# FlightPCB.net
KiCad netlist of a schematic drawn in EAGLE
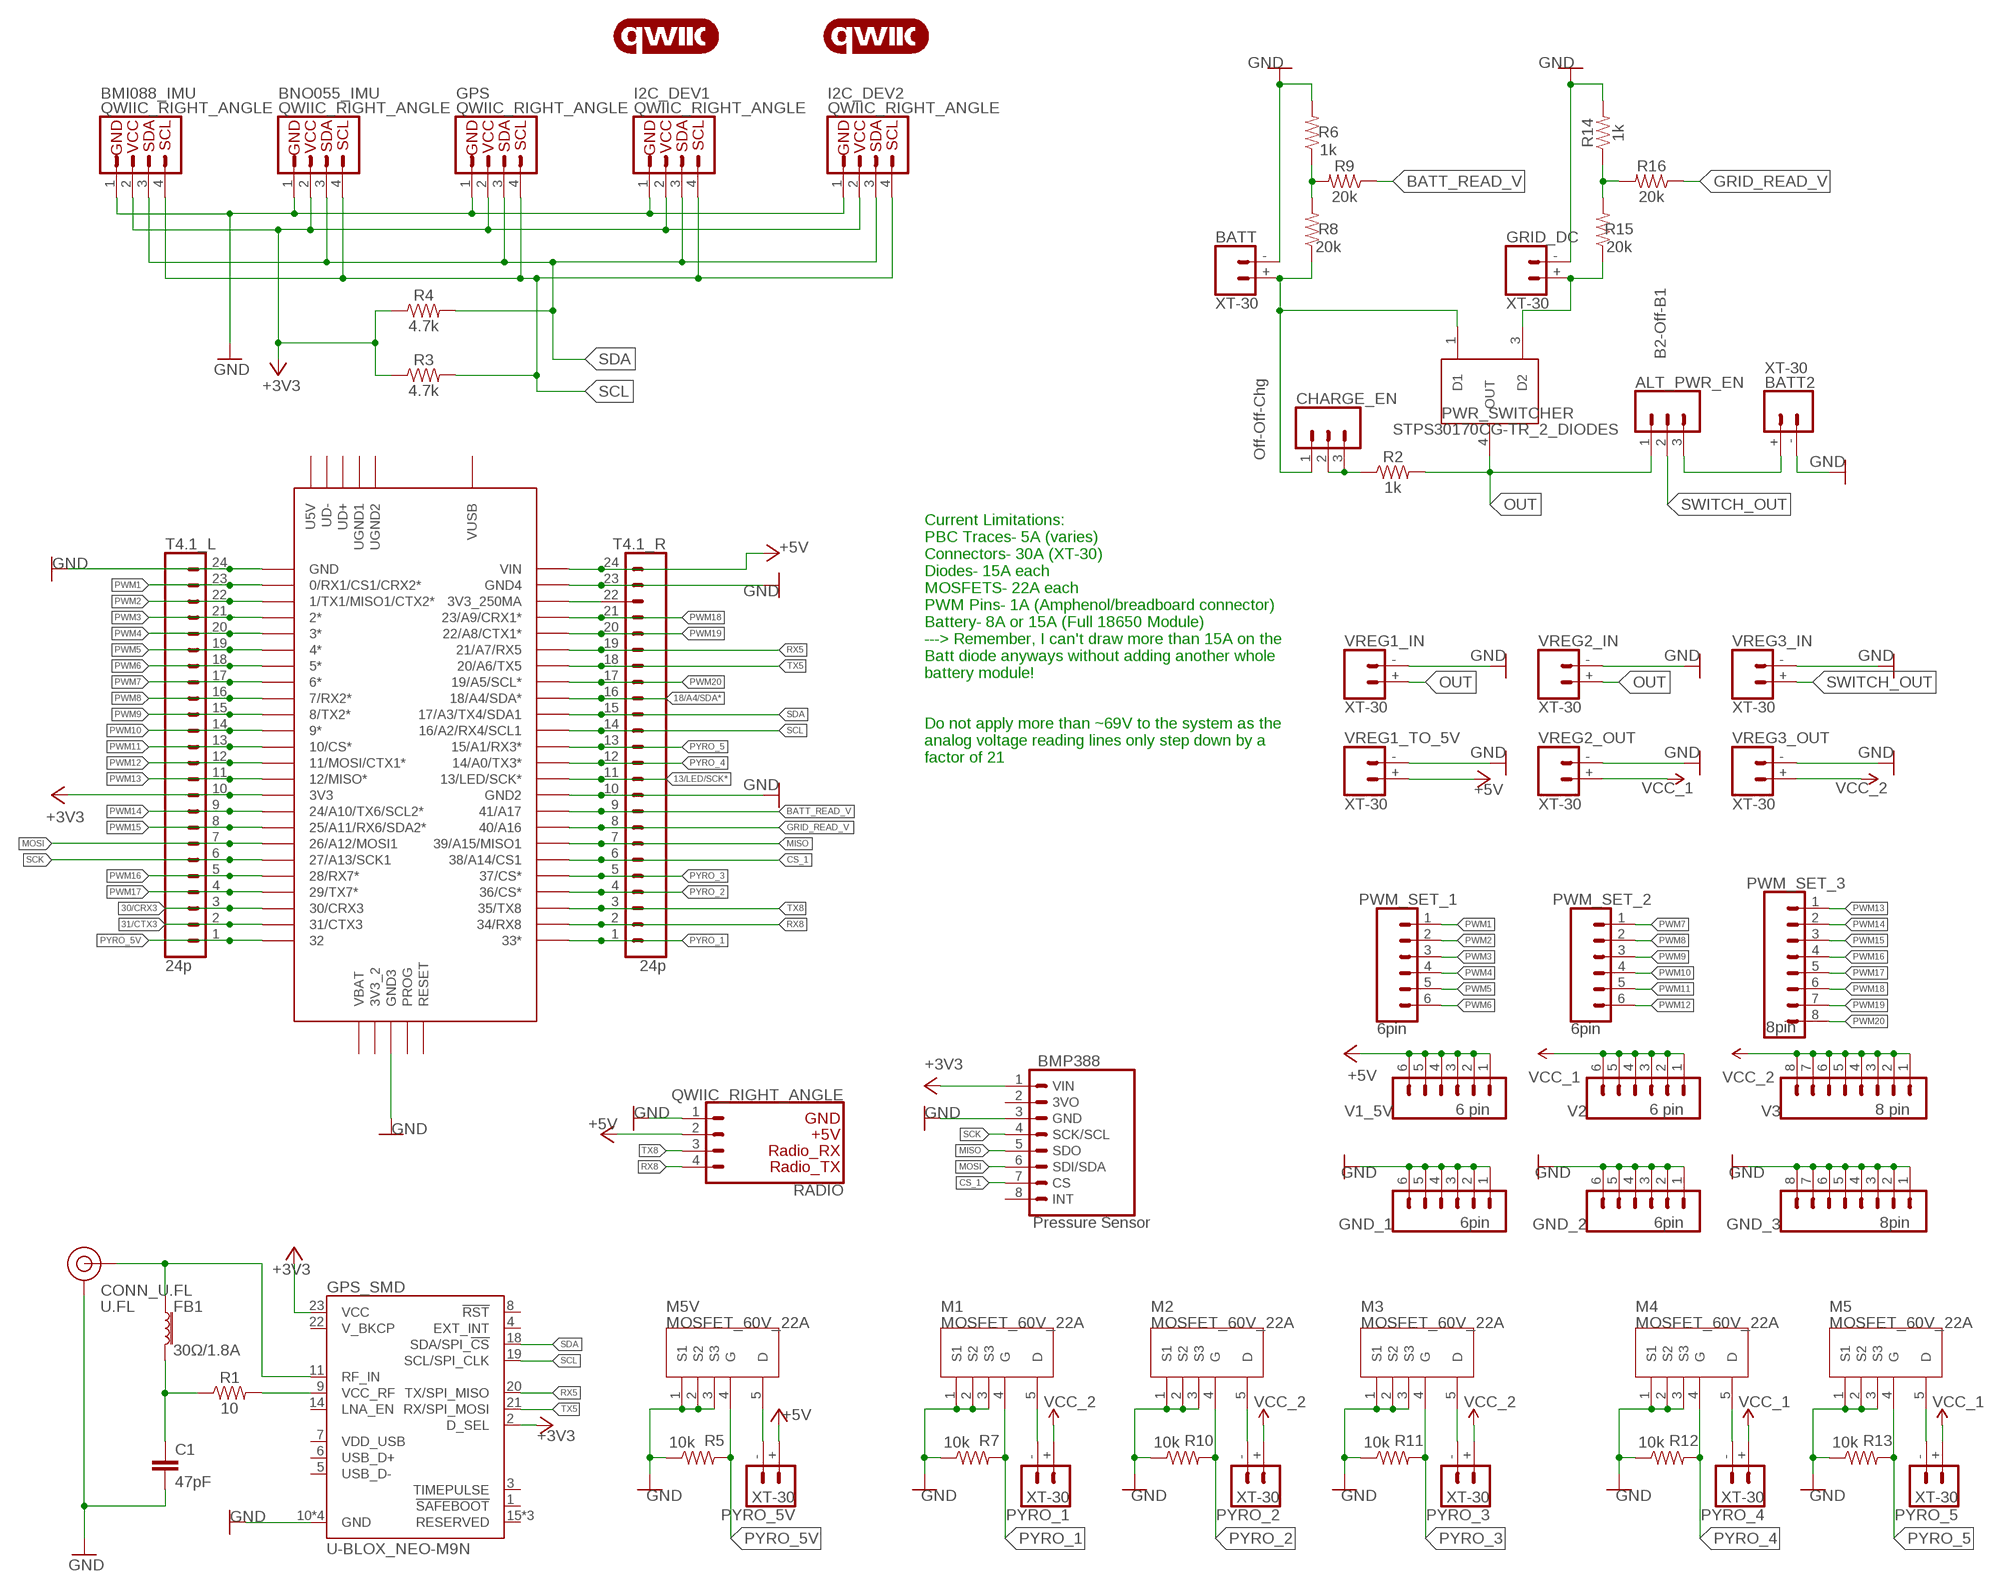
[diagram p0: schematic, sheet 1]

(export (version "E")
  (design (tool "Eeschema 10.0.6"))
  (components
    (comp (ref "ALT_PWR_EN")
      (value "B2-Off-B1")
      (footprint "eagle-import:1X03_SLIDE_SWITCH_EG5137")
      (libsource (lib "eagle-import") (part "CONN_03_SLIDE_SWITCH_EG5137"))
    )
    (comp (ref "BATT")
      (value "XT-30")
      (footprint "eagle-import:1X02_BIG_XT-30")
      (libsource (lib "eagle-import") (part "CONN_02_XT-30_CONNECTOR1X02_XT-30"))
    )
    (comp (ref "BATT2")
      (value "XT-30")
      (footprint "eagle-import:1X02_BIG_XT-30")
      (libsource (lib "eagle-import") (part "CONN_02_XT-30_CONNECTOR1X02_XT-30"))
    )
    (comp (ref "BMI088_IMU")
      (value "QWIIC_RIGHT_ANGLE")
      (footprint "eagle-import:JST04_1MM_RA")
      (libsource (lib "eagle-import") (part "QWIIC_CONNECTORJS-1MM"))
    )
    (comp (ref "BMP388")
      (value "Pressure Sensor")
      (footprint "eagle-import:1X08_FEMALE_LOCK")
      (libsource (lib "eagle-import") (part "CONN_08_BMP388_MODIFIEDFEMALE_LOCK"))
    )
    (comp (ref "BNO055_IMU")
      (value "QWIIC_RIGHT_ANGLE")
      (footprint "eagle-import:JST04_1MM_RA")
      (libsource (lib "eagle-import") (part "QWIIC_CONNECTORJS-1MM"))
    )
    (comp (ref "C1")
      (value "47pF")
      (footprint "eagle-import:0603")
      (libsource (lib "eagle-import") (part "47PF-0603-50V-5%"))
    )
    (comp (ref "CHARGE_EN")
      (value "Off-Off-Chg")
      (footprint "eagle-import:1X03_SLIDE_SWITCH_EG5137")
      (libsource (lib "eagle-import") (part "CONN_03_SLIDE_SWITCH_EG5137"))
    )
    (comp (ref "CONN_U.FL")
      (value "U.FL")
      (footprint "eagle-import:U.FL")
      (libsource (lib "eagle-import") (part "U.FL2PIN"))
    )
    (comp (ref "FB1")
      (value "30Ω/1.8A")
      (footprint "eagle-import:0603")
      (libsource (lib "eagle-import") (part "FERRITE_BEAD-0603"))
    )
    (comp (ref "GND_1")
      (value "6pin")
      (footprint "eagle-import:1X06_LOCK")
      (libsource (lib "eagle-import") (part "CONN_06LOCK"))
    )
    (comp (ref "GND_2")
      (value "6pin")
      (footprint "eagle-import:1X06_LOCK")
      (libsource (lib "eagle-import") (part "CONN_06LOCK"))
    )
    (comp (ref "GND_3")
      (value "8pin")
      (footprint "eagle-import:1X08_LOCK")
      (libsource (lib "eagle-import") (part "CONN_08LOCK"))
    )
    (comp (ref "GPS")
      (value "QWIIC_RIGHT_ANGLE")
      (footprint "eagle-import:JST04_1MM_RA")
      (libsource (lib "eagle-import") (part "QWIIC_CONNECTORJS-1MM"))
    )
    (comp (ref "GPS_SMD")
      (value "U-BLOX_NEO-M9N")
      (footprint "eagle-import:NEO-M9N_M8T_M8U")
      (libsource (lib "eagle-import") (part "U-BLOX_NEO-M9N"))
    )
    (comp (ref "GRID_DC")
      (value "XT-30")
      (footprint "eagle-import:1X02_BIG_XT-30")
      (libsource (lib "eagle-import") (part "CONN_02_XT-30_CONNECTOR1X02_XT-30"))
    )
    (comp (ref "I2C_DEV1")
      (value "QWIIC_RIGHT_ANGLE")
      (footprint "eagle-import:JST04_1MM_RA")
      (libsource (lib "eagle-import") (part "QWIIC_CONNECTORJS-1MM"))
    )
    (comp (ref "I2C_DEV2")
      (value "QWIIC_RIGHT_ANGLE")
      (footprint "eagle-import:JST04_1MM_RA")
      (libsource (lib "eagle-import") (part "QWIIC_CONNECTORJS-1MM"))
    )
    (comp (ref "LOGO1")
      (value "QWIIC_LOGO_CONNECTOR")
      (footprint "eagle-import:QWIIC_5.5MM")
      (libsource (lib "eagle-import") (part "QWIIC_LOGO_CONNECTOR"))
    )
    (comp (ref "LOGO2")
      (value "QWIIC_LOGO_CONNECTOR")
      (footprint "eagle-import:QWIIC_5.5MM")
      (libsource (lib "eagle-import") (part "QWIIC_LOGO_CONNECTOR"))
    )
    (comp (ref "M1")
      (value "MOSFET_60V_22A")
      (footprint "eagle-import:TO127P600X120-5N")
      (libsource (lib "eagle-import") (part "MOSFET_60V_22A"))
    )
    (comp (ref "M2")
      (value "MOSFET_60V_22A")
      (footprint "eagle-import:TO127P600X120-5N")
      (libsource (lib "eagle-import") (part "MOSFET_60V_22A"))
    )
    (comp (ref "M3")
      (value "MOSFET_60V_22A")
      (footprint "eagle-import:TO127P600X120-5N")
      (libsource (lib "eagle-import") (part "MOSFET_60V_22A"))
    )
    (comp (ref "M4")
      (value "MOSFET_60V_22A")
      (footprint "eagle-import:TO127P600X120-5N")
      (libsource (lib "eagle-import") (part "MOSFET_60V_22A"))
    )
    (comp (ref "M5")
      (value "MOSFET_60V_22A")
      (footprint "eagle-import:TO127P600X120-5N")
      (libsource (lib "eagle-import") (part "MOSFET_60V_22A"))
    )
    (comp (ref "M5V")
      (value "MOSFET_60V_22A")
      (footprint "eagle-import:TO127P600X120-5N")
      (libsource (lib "eagle-import") (part "MOSFET_60V_22A"))
    )
    (comp (ref "PWM_SET_1")
      (value "6pin")
      (footprint "eagle-import:1X06_LOCK")
      (libsource (lib "eagle-import") (part "CONN_06LOCK"))
    )
    (comp (ref "PWM_SET_2")
      (value "6pin")
      (footprint "eagle-import:1X06_LOCK")
      (libsource (lib "eagle-import") (part "CONN_06LOCK"))
    )
    (comp (ref "PWM_SET_3")
      (value "8pin")
      (footprint "eagle-import:1X08_LOCK")
      (libsource (lib "eagle-import") (part "CONN_08LOCK"))
    )
    (comp (ref "PWR_SWITCHER")
      (value "STPS30170CG-TR_2_DIODES")
      (footprint "eagle-import:TO-263-3_PACKAGE_MIDDLE_PIN_REMOVED")
      (libsource (lib "eagle-import") (part "STPS30170CG-TR_2_DIODES"))
    )
    (comp (ref "PYRO_1")
      (value "XT-30")
      (footprint "eagle-import:1X02_BIG_XT-30")
      (libsource (lib "eagle-import") (part "CONN_02_XT-30_CONNECTOR1X02_XT-30"))
    )
    (comp (ref "PYRO_2")
      (value "XT-30")
      (footprint "eagle-import:1X02_BIG_XT-30")
      (libsource (lib "eagle-import") (part "CONN_02_XT-30_CONNECTOR1X02_XT-30"))
    )
    (comp (ref "PYRO_3")
      (value "XT-30")
      (footprint "eagle-import:1X02_BIG_XT-30")
      (libsource (lib "eagle-import") (part "CONN_02_XT-30_CONNECTOR1X02_XT-30"))
    )
    (comp (ref "PYRO_4")
      (value "XT-30")
      (footprint "eagle-import:1X02_BIG_XT-30")
      (libsource (lib "eagle-import") (part "CONN_02_XT-30_CONNECTOR1X02_XT-30"))
    )
    (comp (ref "PYRO_5")
      (value "XT-30")
      (footprint "eagle-import:1X02_BIG_XT-30")
      (libsource (lib "eagle-import") (part "CONN_02_XT-30_CONNECTOR1X02_XT-30"))
    )
    (comp (ref "PYRO_5V")
      (value "XT-30")
      (footprint "eagle-import:1X02_BIG_XT-30")
      (libsource (lib "eagle-import") (part "CONN_02_XT-30_CONNECTOR1X02_XT-30"))
    )
    (comp (ref "R1")
      (value "10")
      (footprint "eagle-import:0603")
      (libsource (lib "eagle-import") (part "10OHM-0603-1/10W-1%"))
    )
    (comp (ref "R2")
      (value "1k")
      (footprint "eagle-import:0603")
      (libsource (lib "eagle-import") (part "1KOHM-0603-1/10W-1%"))
    )
    (comp (ref "R3")
      (value "4.7k")
      (footprint "eagle-import:0603")
      (libsource (lib "eagle-import") (part "4.7KOHM-0603-1/10W-1%"))
    )
    (comp (ref "R4")
      (value "4.7k")
      (footprint "eagle-import:0603")
      (libsource (lib "eagle-import") (part "4.7KOHM-0603-1/10W-1%"))
    )
    (comp (ref "R5")
      (value "10k")
      (footprint "eagle-import:0603")
      (libsource (lib "eagle-import") (part "10KOHM-0603-1/10W-1%"))
    )
    (comp (ref "R6")
      (value "1k")
      (footprint "eagle-import:0603")
      (libsource (lib "eagle-import") (part "1KOHM-0603-1/10W-1%"))
    )
    (comp (ref "R7")
      (value "10k")
      (footprint "eagle-import:0603")
      (libsource (lib "eagle-import") (part "10KOHM-0603-1/10W-1%"))
    )
    (comp (ref "R8")
      (value "20k")
      (footprint "eagle-import:0603")
      (libsource (lib "eagle-import") (part "20KOHM-0603-1/10W-1%"))
    )
    (comp (ref "R9")
      (value "20k")
      (footprint "eagle-import:0603")
      (libsource (lib "eagle-import") (part "20KOHM-0603-1/10W-1%"))
    )
    (comp (ref "R10")
      (value "10k")
      (footprint "eagle-import:0603")
      (libsource (lib "eagle-import") (part "10KOHM-0603-1/10W-1%"))
    )
    (comp (ref "R11")
      (value "10k")
      (footprint "eagle-import:0603")
      (libsource (lib "eagle-import") (part "10KOHM-0603-1/10W-1%"))
    )
    (comp (ref "R12")
      (value "10k")
      (footprint "eagle-import:0603")
      (libsource (lib "eagle-import") (part "10KOHM-0603-1/10W-1%"))
    )
    (comp (ref "R13")
      (value "10k")
      (footprint "eagle-import:0603")
      (libsource (lib "eagle-import") (part "10KOHM-0603-1/10W-1%"))
    )
    (comp (ref "R14")
      (value "1k")
      (footprint "eagle-import:0603")
      (libsource (lib "eagle-import") (part "1KOHM-0603-1/10W-1%"))
    )
    (comp (ref "R15")
      (value "20k")
      (footprint "eagle-import:0603")
      (libsource (lib "eagle-import") (part "20KOHM-0603-1/10W-1%"))
    )
    (comp (ref "R16")
      (value "20k")
      (footprint "eagle-import:0603")
      (libsource (lib "eagle-import") (part "20KOHM-0603-1/10W-1%"))
    )
    (comp (ref "RADIO")
      (value "QWIIC_RIGHT_ANGLE")
      (footprint "eagle-import:JST04_1MM_RA")
      (libsource (lib "eagle-import") (part "QWIIC_CONNECTOR_SERIAL_RADIO_MODIFIEDJS-1MM"))
    )
    (comp (ref "T4.1_L")
      (value "24p")
      (footprint "eagle-import:1X24_LOCK")
      (libsource (lib "eagle-import") (part "CONN_24LOCK"))
    )
    (comp (ref "T4.1_R")
      (value "24p")
      (footprint "eagle-import:1X24_LOCK")
      (libsource (lib "eagle-import") (part "CONN_24LOCK"))
    )
    (comp (ref "TEENSY_4.1")
      (value "TEENSY_4.1")
      (footprint "eagle-import:TEENSY_4.1")
      (libsource (lib "eagle-import") (part "TEENSY_4.1"))
    )
    (comp (ref "V1_5V")
      (value "6 pin")
      (footprint "eagle-import:1X06_LOCK")
      (libsource (lib "eagle-import") (part "CONN_06LOCK"))
    )
    (comp (ref "V2")
      (value "6 pin")
      (footprint "eagle-import:1X06_LOCK")
      (libsource (lib "eagle-import") (part "CONN_06LOCK"))
    )
    (comp (ref "V3")
      (value "8 pin")
      (footprint "eagle-import:1X08_LOCK")
      (libsource (lib "eagle-import") (part "CONN_08LOCK"))
    )
    (comp (ref "VREG1_IN")
      (value "XT-30")
      (footprint "eagle-import:1X02_BIG_XT-30")
      (libsource (lib "eagle-import") (part "CONN_02_XT-30_CONNECTOR1X02_XT-30"))
    )
    (comp (ref "VREG1_TO_5V")
      (value "XT-30")
      (footprint "eagle-import:1X02_BIG_XT-30")
      (libsource (lib "eagle-import") (part "CONN_02_XT-30_CONNECTOR1X02_XT-30"))
    )
    (comp (ref "VREG2_IN")
      (value "XT-30")
      (footprint "eagle-import:1X02_BIG_XT-30")
      (libsource (lib "eagle-import") (part "CONN_02_XT-30_CONNECTOR1X02_XT-30"))
    )
    (comp (ref "VREG2_OUT")
      (value "XT-30")
      (footprint "eagle-import:1X02_BIG_XT-30")
      (libsource (lib "eagle-import") (part "CONN_02_XT-30_CONNECTOR1X02_XT-30"))
    )
    (comp (ref "VREG3_IN")
      (value "XT-30")
      (footprint "eagle-import:1X02_BIG_XT-30")
      (libsource (lib "eagle-import") (part "CONN_02_XT-30_CONNECTOR1X02_XT-30"))
    )
    (comp (ref "VREG3_OUT")
      (value "XT-30")
      (footprint "eagle-import:1X02_BIG_XT-30")
      (libsource (lib "eagle-import") (part "CONN_02_XT-30_CONNECTOR1X02_XT-30"))
    )
  )
  (nets
    (net (code "1") (name "+3V3") (class "Default")
      (node (ref "BMI088_IMU") (pin "2") (pinfunction "2_2") (pintype "power_in"))
      (node (ref "BMP388") (pin "1") (pinfunction "VIN_1") (pintype "passive"))
      (node (ref "BNO055_IMU") (pin "2") (pinfunction "2_2") (pintype "power_in"))
      (node (ref "GPS") (pin "2") (pinfunction "2_2") (pintype "power_in"))
      (node (ref "GPS_SMD") (pin "2") (pinfunction "D_SEL_2") (pintype "bidirectional"))
      (node (ref "GPS_SMD") (pin "23") (pinfunction "VCC_23") (pintype "bidirectional"))
      (node (ref "I2C_DEV1") (pin "2") (pinfunction "2_2") (pintype "power_in"))
      (node (ref "I2C_DEV2") (pin "2") (pinfunction "2_2") (pintype "power_in"))
      (node (ref "R3") (pin "1") (pinfunction "1_1") (pintype "passive"))
      (node (ref "R4") (pin "1") (pinfunction "1_1") (pintype "passive"))
      (node (ref "T4.1_L") (pin "10") (pinfunction "10_10") (pintype "passive"))
      (node (ref "TEENSY_4.1") (pin "3V3") (pinfunction "3V3_3V3") (pintype "bidirectional"))
    )
    (net (code "2") (name "+5V") (class "Default")
      (node (ref "PYRO_5V") (pin "+") (pinfunction "+_+") (pintype "passive"))
      (node (ref "RADIO") (pin "2") (pinfunction "2_2") (pintype "power_in"))
      (node (ref "T4.1_R") (pin "24") (pinfunction "24_24") (pintype "passive"))
      (node (ref "TEENSY_4.1") (pin "VIN") (pinfunction "VIN_VIN") (pintype "bidirectional"))
      (node (ref "V1_5V") (pin "1") (pinfunction "1_1") (pintype "passive"))
      (node (ref "V1_5V") (pin "2") (pinfunction "2_2") (pintype "passive"))
      (node (ref "V1_5V") (pin "3") (pinfunction "3_3") (pintype "passive"))
      (node (ref "V1_5V") (pin "4") (pinfunction "4_4") (pintype "passive"))
      (node (ref "V1_5V") (pin "5") (pinfunction "5_5") (pintype "passive"))
      (node (ref "V1_5V") (pin "6") (pinfunction "6_6") (pintype "passive"))
      (node (ref "VREG1_TO_5V") (pin "+") (pinfunction "+_+") (pintype "passive"))
    )
    (net (code "3") (name "13{slash}LED{slash}SCK*") (class "Default")
      (node (ref "T4.1_R") (pin "11") (pinfunction "11_11") (pintype "passive"))
      (node (ref "TEENSY_4.1") (pin "13/LED/SCK*") (pinfunction "13/LED/SCK*_13/LED/SCK*") (pintype "bidirectional"))
    )
    (net (code "4") (name "18{slash}A4{slash}SDA*") (class "Default")
      (node (ref "T4.1_R") (pin "16") (pinfunction "16_16") (pintype "passive"))
      (node (ref "TEENSY_4.1") (pin "18/A4/SDA*") (pinfunction "18/A4/SDA*_18/A4/SDA*") (pintype "bidirectional"))
    )
    (net (code "5") (name "30{slash}CRX3") (class "Default")
      (node (ref "T4.1_L") (pin "3") (pinfunction "3_3") (pintype "passive"))
      (node (ref "TEENSY_4.1") (pin "30/CRX3") (pinfunction "30/CRX3_30/CRX3") (pintype "bidirectional"))
    )
    (net (code "6") (name "31{slash}CTX3") (class "Default")
      (node (ref "T4.1_L") (pin "2") (pinfunction "2_2") (pintype "passive"))
      (node (ref "TEENSY_4.1") (pin "31/CTX3") (pinfunction "31/CTX3_31/CTX3") (pintype "bidirectional"))
    )
    (net (code "7") (name "BATT_READ_V") (class "Default")
      (node (ref "R9") (pin "1") (pinfunction "1_1") (pintype "passive"))
      (node (ref "T4.1_R") (pin "9") (pinfunction "9_9") (pintype "passive"))
      (node (ref "TEENSY_4.1") (pin "41/A17") (pinfunction "41/A17_41/A17") (pintype "bidirectional"))
    )
    (net (code "8") (name "CS_1") (class "Default")
      (node (ref "BMP388") (pin "7") (pinfunction "CS_7") (pintype "passive"))
      (node (ref "T4.1_R") (pin "6") (pinfunction "6_6") (pintype "passive"))
      (node (ref "TEENSY_4.1") (pin "38/A14/CS1") (pinfunction "38/A14/CS1_38/A14/CS1") (pintype "bidirectional"))
    )
    (net (code "9") (name "GND") (class "Default")
      (node (ref "BATT") (pin "-") (pinfunction "-_-") (pintype "passive"))
      (node (ref "BATT2") (pin "-") (pinfunction "-_-") (pintype "passive"))
      (node (ref "BMI088_IMU") (pin "1") (pinfunction "1_1") (pintype "power_in"))
      (node (ref "BMP388") (pin "3") (pinfunction "GND_3") (pintype "passive"))
      (node (ref "BNO055_IMU") (pin "1") (pinfunction "1_1") (pintype "power_in"))
      (node (ref "C1") (pin "2") (pinfunction "2_2") (pintype "passive"))
      (node (ref "CONN_U.FL") (pin "1") (pinfunction "GND_1") (pintype "bidirectional"))
      (node (ref "CONN_U.FL") (pin "2") (pinfunction "GND_2") (pintype "bidirectional"))
      (node (ref "GND_1") (pin "1") (pinfunction "1_1") (pintype "passive"))
      (node (ref "GND_1") (pin "2") (pinfunction "2_2") (pintype "passive"))
      (node (ref "GND_1") (pin "3") (pinfunction "3_3") (pintype "passive"))
      (node (ref "GND_1") (pin "4") (pinfunction "4_4") (pintype "passive"))
      (node (ref "GND_1") (pin "5") (pinfunction "5_5") (pintype "passive"))
      (node (ref "GND_1") (pin "6") (pinfunction "6_6") (pintype "passive"))
      (node (ref "GND_2") (pin "1") (pinfunction "1_1") (pintype "passive"))
      (node (ref "GND_2") (pin "2") (pinfunction "2_2") (pintype "passive"))
      (node (ref "GND_2") (pin "3") (pinfunction "3_3") (pintype "passive"))
      (node (ref "GND_2") (pin "4") (pinfunction "4_4") (pintype "passive"))
      (node (ref "GND_2") (pin "5") (pinfunction "5_5") (pintype "passive"))
      (node (ref "GND_2") (pin "6") (pinfunction "6_6") (pintype "passive"))
      (node (ref "GND_3") (pin "1") (pinfunction "1_1") (pintype "passive"))
      (node (ref "GND_3") (pin "2") (pinfunction "2_2") (pintype "passive"))
      (node (ref "GND_3") (pin "3") (pinfunction "3_3") (pintype "passive"))
      (node (ref "GND_3") (pin "4") (pinfunction "4_4") (pintype "passive"))
      (node (ref "GND_3") (pin "5") (pinfunction "5_5") (pintype "passive"))
      (node (ref "GND_3") (pin "6") (pinfunction "6_6") (pintype "passive"))
      (node (ref "GND_3") (pin "7") (pinfunction "7_7") (pintype "passive"))
      (node (ref "GND_3") (pin "8") (pinfunction "8_8") (pintype "passive"))
      (node (ref "GPS") (pin "1") (pinfunction "1_1") (pintype "power_in"))
      (node (ref "GPS_SMD") (pin "10") (pinfunction "GND_10") (pintype "bidirectional"))
      (node (ref "GPS_SMD") (pin "12") (pinfunction "GND_12") (pintype "bidirectional"))
      (node (ref "GPS_SMD") (pin "13") (pinfunction "GND_13") (pintype "bidirectional"))
      (node (ref "GPS_SMD") (pin "24") (pinfunction "GND_24") (pintype "bidirectional"))
      (node (ref "GRID_DC") (pin "-") (pinfunction "-_-") (pintype "passive"))
      (node (ref "I2C_DEV1") (pin "1") (pinfunction "1_1") (pintype "power_in"))
      (node (ref "I2C_DEV2") (pin "1") (pinfunction "1_1") (pintype "power_in"))
      (node (ref "M1") (pin "1") (pinfunction "S1_1") (pintype "bidirectional"))
      (node (ref "M1") (pin "2") (pinfunction "S2_2") (pintype "bidirectional"))
      (node (ref "M1") (pin "3") (pinfunction "S3_3") (pintype "bidirectional"))
      (node (ref "M2") (pin "1") (pinfunction "S1_1") (pintype "bidirectional"))
      (node (ref "M2") (pin "2") (pinfunction "S2_2") (pintype "bidirectional"))
      (node (ref "M2") (pin "3") (pinfunction "S3_3") (pintype "bidirectional"))
      (node (ref "M3") (pin "1") (pinfunction "S1_1") (pintype "bidirectional"))
      (node (ref "M3") (pin "2") (pinfunction "S2_2") (pintype "bidirectional"))
      (node (ref "M3") (pin "3") (pinfunction "S3_3") (pintype "bidirectional"))
      (node (ref "M4") (pin "1") (pinfunction "S1_1") (pintype "bidirectional"))
      (node (ref "M4") (pin "2") (pinfunction "S2_2") (pintype "bidirectional"))
      (node (ref "M4") (pin "3") (pinfunction "S3_3") (pintype "bidirectional"))
      (node (ref "M5") (pin "1") (pinfunction "S1_1") (pintype "bidirectional"))
      (node (ref "M5") (pin "2") (pinfunction "S2_2") (pintype "bidirectional"))
      (node (ref "M5") (pin "3") (pinfunction "S3_3") (pintype "bidirectional"))
      (node (ref "M5V") (pin "1") (pinfunction "S1_1") (pintype "bidirectional"))
      (node (ref "M5V") (pin "2") (pinfunction "S2_2") (pintype "bidirectional"))
      (node (ref "M5V") (pin "3") (pinfunction "S3_3") (pintype "bidirectional"))
      (node (ref "R10") (pin "1") (pinfunction "1_1") (pintype "passive"))
      (node (ref "R11") (pin "1") (pinfunction "1_1") (pintype "passive"))
      (node (ref "R12") (pin "1") (pinfunction "1_1") (pintype "passive"))
      (node (ref "R13") (pin "1") (pinfunction "1_1") (pintype "passive"))
      (node (ref "R14") (pin "2") (pinfunction "2_2") (pintype "passive"))
      (node (ref "R5") (pin "1") (pinfunction "1_1") (pintype "passive"))
      (node (ref "R6") (pin "2") (pinfunction "2_2") (pintype "passive"))
      (node (ref "R7") (pin "1") (pinfunction "1_1") (pintype "passive"))
      (node (ref "RADIO") (pin "1") (pinfunction "1_1") (pintype "power_in"))
      (node (ref "T4.1_L") (pin "24") (pinfunction "24_24") (pintype "passive"))
      (node (ref "T4.1_R") (pin "10") (pinfunction "10_10") (pintype "passive"))
      (node (ref "T4.1_R") (pin "23") (pinfunction "23_23") (pintype "passive"))
      (node (ref "TEENSY_4.1") (pin "GND") (pinfunction "GND_GND") (pintype "bidirectional"))
      (node (ref "TEENSY_4.1") (pin "GND2") (pinfunction "GND2_GND2") (pintype "bidirectional"))
      (node (ref "TEENSY_4.1") (pin "GND3") (pinfunction "GND3_GND3") (pintype "bidirectional"))
      (node (ref "TEENSY_4.1") (pin "GND4") (pinfunction "GND4_GND4") (pintype "bidirectional"))
      (node (ref "VREG1_IN") (pin "-") (pinfunction "-_-") (pintype "passive"))
      (node (ref "VREG1_TO_5V") (pin "-") (pinfunction "-_-") (pintype "passive"))
      (node (ref "VREG2_IN") (pin "-") (pinfunction "-_-") (pintype "passive"))
      (node (ref "VREG2_OUT") (pin "-") (pinfunction "-_-") (pintype "passive"))
      (node (ref "VREG3_IN") (pin "-") (pinfunction "-_-") (pintype "passive"))
      (node (ref "VREG3_OUT") (pin "-") (pinfunction "-_-") (pintype "passive"))
    )
    (net (code "10") (name "GRID_READ_V") (class "Default")
      (node (ref "R16") (pin "1") (pinfunction "1_1") (pintype "passive"))
      (node (ref "T4.1_R") (pin "8") (pinfunction "8_8") (pintype "passive"))
      (node (ref "TEENSY_4.1") (pin "40/A16") (pinfunction "40/A16_40/A16") (pintype "bidirectional"))
    )
    (net (code "11") (name "MISO") (class "Default")
      (node (ref "BMP388") (pin "5") (pinfunction "SDO_5") (pintype "passive"))
      (node (ref "T4.1_R") (pin "7") (pinfunction "7_7") (pintype "passive"))
      (node (ref "TEENSY_4.1") (pin "39/A15/MISO1") (pinfunction "39/A15/MISO1_39/A15/MISO1") (pintype "bidirectional"))
    )
    (net (code "12") (name "MOSI") (class "Default")
      (node (ref "BMP388") (pin "6") (pinfunction "SDI/SDA_6") (pintype "passive"))
      (node (ref "T4.1_L") (pin "7") (pinfunction "7_7") (pintype "passive"))
      (node (ref "TEENSY_4.1") (pin "26/A12/MOSI1") (pinfunction "26/A12/MOSI1_26/A12/MOSI1") (pintype "bidirectional"))
    )
    (net (code "13") (name "Net-(ALT_PWR_EN-Pad3)") (class "Default")
      (node (ref "ALT_PWR_EN") (pin "3") (pinfunction "3_3") (pintype "passive"))
      (node (ref "BATT2") (pin "+") (pinfunction "+_+") (pintype "passive"))
    )
    (net (code "14") (name "Net-(C1-Pad1)") (class "Default")
      (node (ref "C1") (pin "1") (pinfunction "1_1") (pintype "passive"))
      (node (ref "FB1") (pin "2") (pinfunction "2_2") (pintype "passive"))
      (node (ref "R1") (pin "1") (pinfunction "1_1") (pintype "passive"))
    )
    (net (code "15") (name "Net-(CHARGE_EN-Pad2)") (class "Default")
      (node (ref "CHARGE_EN") (pin "2") (pinfunction "2_2") (pintype "passive"))
      (node (ref "CHARGE_EN") (pin "3") (pinfunction "3_3") (pintype "passive"))
      (node (ref "R2") (pin "1") (pinfunction "1_1") (pintype "passive"))
    )
    (net (code "16") (name "Net-(CONN_U.FL-SIGNAL)") (class "Default")
      (node (ref "CONN_U.FL") (pin "FEED") (pinfunction "SIGNAL_FEED") (pintype "bidirectional"))
      (node (ref "FB1") (pin "1") (pinfunction "1_1") (pintype "passive"))
      (node (ref "GPS_SMD") (pin "11") (pinfunction "RF_IN_11") (pintype "bidirectional"))
    )
    (net (code "17") (name "Net-(GPS_SMD-VCC_RF)") (class "Default")
      (node (ref "GPS_SMD") (pin "9") (pinfunction "VCC_RF_9") (pintype "bidirectional"))
      (node (ref "R1") (pin "2") (pinfunction "2_2") (pintype "passive"))
    )
    (net (code "18") (name "Net-(M1-D)") (class "Default")
      (node (ref "M1") (pin "5") (pinfunction "D_5") (pintype "bidirectional"))
      (node (ref "PYRO_1") (pin "-") (pinfunction "-_-") (pintype "passive"))
    )
    (net (code "19") (name "Net-(M2-D)") (class "Default")
      (node (ref "M2") (pin "5") (pinfunction "D_5") (pintype "bidirectional"))
      (node (ref "PYRO_2") (pin "-") (pinfunction "-_-") (pintype "passive"))
    )
    (net (code "20") (name "Net-(M3-D)") (class "Default")
      (node (ref "M3") (pin "5") (pinfunction "D_5") (pintype "bidirectional"))
      (node (ref "PYRO_3") (pin "-") (pinfunction "-_-") (pintype "passive"))
    )
    (net (code "21") (name "Net-(M4-D)") (class "Default")
      (node (ref "M4") (pin "5") (pinfunction "D_5") (pintype "bidirectional"))
      (node (ref "PYRO_4") (pin "-") (pinfunction "-_-") (pintype "passive"))
    )
    (net (code "22") (name "Net-(M5-D)") (class "Default")
      (node (ref "M5") (pin "5") (pinfunction "D_5") (pintype "bidirectional"))
      (node (ref "PYRO_5") (pin "-") (pinfunction "-_-") (pintype "passive"))
    )
    (net (code "23") (name "Net-(M5V-D)") (class "Default")
      (node (ref "M5V") (pin "5") (pinfunction "D_5") (pintype "bidirectional"))
      (node (ref "PYRO_5V") (pin "-") (pinfunction "-_-") (pintype "passive"))
    )
    (net (code "24") (name "Net-(PWR_SWITCHER-D1)") (class "Default")
      (node (ref "BATT") (pin "+") (pinfunction "+_+") (pintype "passive"))
      (node (ref "CHARGE_EN") (pin "1") (pinfunction "1_1") (pintype "passive"))
      (node (ref "PWR_SWITCHER") (pin "1") (pinfunction "D1_1") (pintype "bidirectional"))
      (node (ref "R8") (pin "1") (pinfunction "1_1") (pintype "passive"))
    )
    (net (code "25") (name "Net-(PWR_SWITCHER-D2)") (class "Default")
      (node (ref "GRID_DC") (pin "+") (pinfunction "+_+") (pintype "passive"))
      (node (ref "PWR_SWITCHER") (pin "3") (pinfunction "D2_3") (pintype "bidirectional"))
      (node (ref "R15") (pin "1") (pinfunction "1_1") (pintype "passive"))
    )
    (net (code "26") (name "Net-(R6-Pad1)") (class "Default")
      (node (ref "R6") (pin "1") (pinfunction "1_1") (pintype "passive"))
      (node (ref "R8") (pin "2") (pinfunction "2_2") (pintype "passive"))
      (node (ref "R9") (pin "2") (pinfunction "2_2") (pintype "passive"))
    )
    (net (code "27") (name "Net-(R14-Pad1)") (class "Default")
      (node (ref "R14") (pin "1") (pinfunction "1_1") (pintype "passive"))
      (node (ref "R15") (pin "2") (pinfunction "2_2") (pintype "passive"))
      (node (ref "R16") (pin "2") (pinfunction "2_2") (pintype "passive"))
    )
    (net (code "28") (name "Net-(T4.1_R-Pad22)") (class "Default")
      (node (ref "T4.1_R") (pin "22") (pinfunction "22_22") (pintype "passive"))
      (node (ref "TEENSY_4.1") (pin "3V3_250MA") (pinfunction "3V3_250MA_3V3_250MA") (pintype "bidirectional"))
    )
    (net (code "29") (name "OUT") (class "Default")
      (node (ref "ALT_PWR_EN") (pin "1") (pinfunction "1_1") (pintype "passive"))
      (node (ref "PWR_SWITCHER") (pin "4") (pinfunction "OUT_4") (pintype "bidirectional"))
      (node (ref "R2") (pin "2") (pinfunction "2_2") (pintype "passive"))
      (node (ref "VREG1_IN") (pin "+") (pinfunction "+_+") (pintype "passive"))
      (node (ref "VREG2_IN") (pin "+") (pinfunction "+_+") (pintype "passive"))
    )
    (net (code "30") (name "PWM1") (class "Default")
      (node (ref "PWM_SET_1") (pin "1") (pinfunction "1_1") (pintype "passive"))
      (node (ref "T4.1_L") (pin "23") (pinfunction "23_23") (pintype "passive"))
      (node (ref "TEENSY_4.1") (pin "0/RX1/CS1/CRX2*") (pinfunction "0/RX1/CS1/CRX2*_0/RX1/CS1/CRX2*") (pintype "bidirectional"))
    )
    (net (code "31") (name "PWM2") (class "Default")
      (node (ref "PWM_SET_1") (pin "2") (pinfunction "2_2") (pintype "passive"))
      (node (ref "T4.1_L") (pin "22") (pinfunction "22_22") (pintype "passive"))
      (node (ref "TEENSY_4.1") (pin "1/TX1/MISO1/CTX2*") (pinfunction "1/TX1/MISO1/CTX2*_1/TX1/MISO1/CTX2*") (pintype "bidirectional"))
    )
    (net (code "32") (name "PWM3") (class "Default")
      (node (ref "PWM_SET_1") (pin "3") (pinfunction "3_3") (pintype "passive"))
      (node (ref "T4.1_L") (pin "21") (pinfunction "21_21") (pintype "passive"))
      (node (ref "TEENSY_4.1") (pin "2*") (pinfunction "2*_2*") (pintype "bidirectional"))
    )
    (net (code "33") (name "PWM4") (class "Default")
      (node (ref "PWM_SET_1") (pin "4") (pinfunction "4_4") (pintype "passive"))
      (node (ref "T4.1_L") (pin "20") (pinfunction "20_20") (pintype "passive"))
      (node (ref "TEENSY_4.1") (pin "3*") (pinfunction "3*_3*") (pintype "bidirectional"))
    )
    (net (code "34") (name "PWM5") (class "Default")
      (node (ref "PWM_SET_1") (pin "5") (pinfunction "5_5") (pintype "passive"))
      (node (ref "T4.1_L") (pin "19") (pinfunction "19_19") (pintype "passive"))
      (node (ref "TEENSY_4.1") (pin "4*") (pinfunction "4*_4*") (pintype "bidirectional"))
    )
    (net (code "35") (name "PWM6") (class "Default")
      (node (ref "PWM_SET_1") (pin "6") (pinfunction "6_6") (pintype "passive"))
      (node (ref "T4.1_L") (pin "18") (pinfunction "18_18") (pintype "passive"))
      (node (ref "TEENSY_4.1") (pin "5*") (pinfunction "5*_5*") (pintype "bidirectional"))
    )
    (net (code "36") (name "PWM7") (class "Default")
      (node (ref "PWM_SET_2") (pin "1") (pinfunction "1_1") (pintype "passive"))
      (node (ref "T4.1_L") (pin "17") (pinfunction "17_17") (pintype "passive"))
      (node (ref "TEENSY_4.1") (pin "6*") (pinfunction "6*_6*") (pintype "bidirectional"))
    )
    (net (code "37") (name "PWM8") (class "Default")
      (node (ref "PWM_SET_2") (pin "2") (pinfunction "2_2") (pintype "passive"))
      (node (ref "T4.1_L") (pin "16") (pinfunction "16_16") (pintype "passive"))
      (node (ref "TEENSY_4.1") (pin "7/RX2*") (pinfunction "7/RX2*_7/RX2*") (pintype "bidirectional"))
    )
    (net (code "38") (name "PWM9") (class "Default")
      (node (ref "PWM_SET_2") (pin "3") (pinfunction "3_3") (pintype "passive"))
      (node (ref "T4.1_L") (pin "15") (pinfunction "15_15") (pintype "passive"))
      (node (ref "TEENSY_4.1") (pin "8/TX2*") (pinfunction "8/TX2*_8/TX2*") (pintype "bidirectional"))
    )
    (net (code "39") (name "PWM10") (class "Default")
      (node (ref "PWM_SET_2") (pin "4") (pinfunction "4_4") (pintype "passive"))
      (node (ref "T4.1_L") (pin "14") (pinfunction "14_14") (pintype "passive"))
      (node (ref "TEENSY_4.1") (pin "9*") (pinfunction "9*_9*") (pintype "bidirectional"))
    )
    (net (code "40") (name "PWM11") (class "Default")
      (node (ref "PWM_SET_2") (pin "5") (pinfunction "5_5") (pintype "passive"))
      (node (ref "T4.1_L") (pin "13") (pinfunction "13_13") (pintype "passive"))
      (node (ref "TEENSY_4.1") (pin "10/CS*") (pinfunction "10/CS*_10/CS*") (pintype "bidirectional"))
    )
    (net (code "41") (name "PWM12") (class "Default")
      (node (ref "PWM_SET_2") (pin "6") (pinfunction "6_6") (pintype "passive"))
      (node (ref "T4.1_L") (pin "12") (pinfunction "12_12") (pintype "passive"))
      (node (ref "TEENSY_4.1") (pin "11/MOSI/CTX1*") (pinfunction "11/MOSI/CTX1*_11/MOSI/CTX1*") (pintype "bidirectional"))
    )
    (net (code "42") (name "PWM13") (class "Default")
      (node (ref "PWM_SET_3") (pin "1") (pinfunction "1_1") (pintype "passive"))
      (node (ref "T4.1_L") (pin "11") (pinfunction "11_11") (pintype "passive"))
      (node (ref "TEENSY_4.1") (pin "12/MISO*") (pinfunction "12/MISO*_12/MISO*") (pintype "bidirectional"))
    )
    (net (code "43") (name "PWM14") (class "Default")
      (node (ref "PWM_SET_3") (pin "2") (pinfunction "2_2") (pintype "passive"))
      (node (ref "T4.1_L") (pin "9") (pinfunction "9_9") (pintype "passive"))
      (node (ref "TEENSY_4.1") (pin "24/A10/TX6/SCL2*") (pinfunction "24/A10/TX6/SCL2*_24/A10/TX6/SCL2*") (pintype "bidirectional"))
    )
    (net (code "44") (name "PWM15") (class "Default")
      (node (ref "PWM_SET_3") (pin "3") (pinfunction "3_3") (pintype "passive"))
      (node (ref "T4.1_L") (pin "8") (pinfunction "8_8") (pintype "passive"))
      (node (ref "TEENSY_4.1") (pin "25/A11/RX6/SDA2*") (pinfunction "25/A11/RX6/SDA2*_25/A11/RX6/SDA2*") (pintype "bidirectional"))
    )
    (net (code "45") (name "PWM16") (class "Default")
      (node (ref "PWM_SET_3") (pin "4") (pinfunction "4_4") (pintype "passive"))
      (node (ref "T4.1_L") (pin "5") (pinfunction "5_5") (pintype "passive"))
      (node (ref "TEENSY_4.1") (pin "28/RX7*") (pinfunction "28/RX7*_28/RX7*") (pintype "bidirectional"))
    )
    (net (code "46") (name "PWM17") (class "Default")
      (node (ref "PWM_SET_3") (pin "5") (pinfunction "5_5") (pintype "passive"))
      (node (ref "T4.1_L") (pin "4") (pinfunction "4_4") (pintype "passive"))
      (node (ref "TEENSY_4.1") (pin "29/TX7*") (pinfunction "29/TX7*_29/TX7*") (pintype "bidirectional"))
    )
    (net (code "47") (name "PWM18") (class "Default")
      (node (ref "PWM_SET_3") (pin "6") (pinfunction "6_6") (pintype "passive"))
      (node (ref "T4.1_R") (pin "21") (pinfunction "21_21") (pintype "passive"))
      (node (ref "TEENSY_4.1") (pin "23/A9/CRX1*") (pinfunction "23/A9/CRX1*_23/A9/CRX1*") (pintype "bidirectional"))
    )
    (net (code "48") (name "PWM19") (class "Default")
      (node (ref "PWM_SET_3") (pin "7") (pinfunction "7_7") (pintype "passive"))
      (node (ref "T4.1_R") (pin "20") (pinfunction "20_20") (pintype "passive"))
      (node (ref "TEENSY_4.1") (pin "22/A8/CTX1*") (pinfunction "22/A8/CTX1*_22/A8/CTX1*") (pintype "bidirectional"))
    )
    (net (code "49") (name "PWM20") (class "Default")
      (node (ref "PWM_SET_3") (pin "8") (pinfunction "8_8") (pintype "passive"))
      (node (ref "T4.1_R") (pin "17") (pinfunction "17_17") (pintype "passive"))
      (node (ref "TEENSY_4.1") (pin "19/A5/SCL*") (pinfunction "19/A5/SCL*_19/A5/SCL*") (pintype "bidirectional"))
    )
    (net (code "50") (name "PYRO_1") (class "Default")
      (node (ref "M1") (pin "4") (pinfunction "G_4") (pintype "bidirectional"))
      (node (ref "R7") (pin "2") (pinfunction "2_2") (pintype "passive"))
      (node (ref "T4.1_R") (pin "1") (pinfunction "1_1") (pintype "passive"))
      (node (ref "TEENSY_4.1") (pin "33*") (pinfunction "33*_33*") (pintype "bidirectional"))
    )
    (net (code "51") (name "PYRO_2") (class "Default")
      (node (ref "M2") (pin "4") (pinfunction "G_4") (pintype "bidirectional"))
      (node (ref "R10") (pin "2") (pinfunction "2_2") (pintype "passive"))
      (node (ref "T4.1_R") (pin "4") (pinfunction "4_4") (pintype "passive"))
      (node (ref "TEENSY_4.1") (pin "36/CS*") (pinfunction "36/CS*_36/CS*") (pintype "bidirectional"))
    )
    (net (code "52") (name "PYRO_3") (class "Default")
      (node (ref "M3") (pin "4") (pinfunction "G_4") (pintype "bidirectional"))
      (node (ref "R11") (pin "2") (pinfunction "2_2") (pintype "passive"))
      (node (ref "T4.1_R") (pin "5") (pinfunction "5_5") (pintype "passive"))
      (node (ref "TEENSY_4.1") (pin "37/CS*") (pinfunction "37/CS*_37/CS*") (pintype "bidirectional"))
    )
    (net (code "53") (name "PYRO_4") (class "Default")
      (node (ref "M4") (pin "4") (pinfunction "G_4") (pintype "bidirectional"))
      (node (ref "R12") (pin "2") (pinfunction "2_2") (pintype "passive"))
      (node (ref "T4.1_R") (pin "12") (pinfunction "12_12") (pintype "passive"))
      (node (ref "TEENSY_4.1") (pin "14/A0/TX3*") (pinfunction "14/A0/TX3*_14/A0/TX3*") (pintype "bidirectional"))
    )
    (net (code "54") (name "PYRO_5") (class "Default")
      (node (ref "M5") (pin "4") (pinfunction "G_4") (pintype "bidirectional"))
      (node (ref "R13") (pin "2") (pinfunction "2_2") (pintype "passive"))
      (node (ref "T4.1_R") (pin "13") (pinfunction "13_13") (pintype "passive"))
      (node (ref "TEENSY_4.1") (pin "15/A1/RX3*") (pinfunction "15/A1/RX3*_15/A1/RX3*") (pintype "bidirectional"))
    )
    (net (code "55") (name "PYRO_5V") (class "Default")
      (node (ref "M5V") (pin "4") (pinfunction "G_4") (pintype "bidirectional"))
      (node (ref "R5") (pin "2") (pinfunction "2_2") (pintype "passive"))
      (node (ref "T4.1_L") (pin "1") (pinfunction "1_1") (pintype "passive"))
      (node (ref "TEENSY_4.1") (pin "32") (pinfunction "32_32") (pintype "bidirectional"))
    )
    (net (code "56") (name "RX5") (class "Default")
      (node (ref "GPS_SMD") (pin "20") (pinfunction "TX/SPI_MISO_20") (pintype "bidirectional"))
      (node (ref "T4.1_R") (pin "19") (pinfunction "19_19") (pintype "passive"))
      (node (ref "TEENSY_4.1") (pin "21/A7/RX5") (pinfunction "21/A7/RX5_21/A7/RX5") (pintype "bidirectional"))
    )
    (net (code "57") (name "RX8") (class "Default")
      (node (ref "RADIO") (pin "4") (pinfunction "4_4") (pintype "passive"))
      (node (ref "T4.1_R") (pin "2") (pinfunction "2_2") (pintype "passive"))
      (node (ref "TEENSY_4.1") (pin "34/RX8") (pinfunction "34/RX8_34/RX8") (pintype "bidirectional"))
    )
    (net (code "58") (name "SCK") (class "Default")
      (node (ref "BMP388") (pin "4") (pinfunction "SCK/SCL_4") (pintype "passive"))
      (node (ref "T4.1_L") (pin "6") (pinfunction "6_6") (pintype "passive"))
      (node (ref "TEENSY_4.1") (pin "27/A13/SCK1") (pinfunction "27/A13/SCK1_27/A13/SCK1") (pintype "bidirectional"))
    )
    (net (code "59") (name "SCL") (class "Default")
      (node (ref "BMI088_IMU") (pin "4") (pinfunction "4_4") (pintype "passive"))
      (node (ref "BNO055_IMU") (pin "4") (pinfunction "4_4") (pintype "passive"))
      (node (ref "GPS") (pin "4") (pinfunction "4_4") (pintype "passive"))
      (node (ref "GPS_SMD") (pin "19") (pinfunction "SCL/SPI_CLK_19") (pintype "bidirectional"))
      (node (ref "I2C_DEV1") (pin "4") (pinfunction "4_4") (pintype "passive"))
      (node (ref "I2C_DEV2") (pin "4") (pinfunction "4_4") (pintype "passive"))
      (node (ref "R3") (pin "2") (pinfunction "2_2") (pintype "passive"))
      (node (ref "T4.1_R") (pin "14") (pinfunction "14_14") (pintype "passive"))
      (node (ref "TEENSY_4.1") (pin "16/A2/RX4/SCL1") (pinfunction "16/A2/RX4/SCL1_16/A2/RX4/SCL1") (pintype "bidirectional"))
    )
    (net (code "60") (name "SDA") (class "Default")
      (node (ref "BMI088_IMU") (pin "3") (pinfunction "3_3") (pintype "passive"))
      (node (ref "BNO055_IMU") (pin "3") (pinfunction "3_3") (pintype "passive"))
      (node (ref "GPS") (pin "3") (pinfunction "3_3") (pintype "passive"))
      (node (ref "GPS_SMD") (pin "18") (pinfunction "SDA/SPI_~{CS}_18") (pintype "bidirectional"))
      (node (ref "I2C_DEV1") (pin "3") (pinfunction "3_3") (pintype "passive"))
      (node (ref "I2C_DEV2") (pin "3") (pinfunction "3_3") (pintype "passive"))
      (node (ref "R4") (pin "2") (pinfunction "2_2") (pintype "passive"))
      (node (ref "T4.1_R") (pin "15") (pinfunction "15_15") (pintype "passive"))
      (node (ref "TEENSY_4.1") (pin "17/A3/TX4/SDA1") (pinfunction "17/A3/TX4/SDA1_17/A3/TX4/SDA1") (pintype "bidirectional"))
    )
    (net (code "61") (name "SWITCH_OUT") (class "Default")
      (node (ref "ALT_PWR_EN") (pin "2") (pinfunction "2_2") (pintype "passive"))
      (node (ref "VREG3_IN") (pin "+") (pinfunction "+_+") (pintype "passive"))
    )
    (net (code "62") (name "TX5") (class "Default")
      (node (ref "GPS_SMD") (pin "21") (pinfunction "RX/SPI_MOSI_21") (pintype "bidirectional"))
      (node (ref "T4.1_R") (pin "18") (pinfunction "18_18") (pintype "passive"))
      (node (ref "TEENSY_4.1") (pin "20/A6/TX5") (pinfunction "20/A6/TX5_20/A6/TX5") (pintype "bidirectional"))
    )
    (net (code "63") (name "TX8") (class "Default")
      (node (ref "RADIO") (pin "3") (pinfunction "3_3") (pintype "passive"))
      (node (ref "T4.1_R") (pin "3") (pinfunction "3_3") (pintype "passive"))
      (node (ref "TEENSY_4.1") (pin "35/TX8") (pinfunction "35/TX8_35/TX8") (pintype "bidirectional"))
    )
    (net (code "64") (name "VCC_1") (class "Default")
      (node (ref "PYRO_4") (pin "+") (pinfunction "+_+") (pintype "passive"))
      (node (ref "PYRO_5") (pin "+") (pinfunction "+_+") (pintype "passive"))
      (node (ref "V2") (pin "1") (pinfunction "1_1") (pintype "passive"))
      (node (ref "V2") (pin "2") (pinfunction "2_2") (pintype "passive"))
      (node (ref "V2") (pin "3") (pinfunction "3_3") (pintype "passive"))
      (node (ref "V2") (pin "4") (pinfunction "4_4") (pintype "passive"))
      (node (ref "V2") (pin "5") (pinfunction "5_5") (pintype "passive"))
      (node (ref "V2") (pin "6") (pinfunction "6_6") (pintype "passive"))
      (node (ref "VREG2_OUT") (pin "+") (pinfunction "+_+") (pintype "passive"))
    )
    (net (code "65") (name "VCC_2") (class "Default")
      (node (ref "PYRO_1") (pin "+") (pinfunction "+_+") (pintype "passive"))
      (node (ref "PYRO_2") (pin "+") (pinfunction "+_+") (pintype "passive"))
      (node (ref "PYRO_3") (pin "+") (pinfunction "+_+") (pintype "passive"))
      (node (ref "V3") (pin "1") (pinfunction "1_1") (pintype "passive"))
      (node (ref "V3") (pin "2") (pinfunction "2_2") (pintype "passive"))
      (node (ref "V3") (pin "3") (pinfunction "3_3") (pintype "passive"))
      (node (ref "V3") (pin "4") (pinfunction "4_4") (pintype "passive"))
      (node (ref "V3") (pin "5") (pinfunction "5_5") (pintype "passive"))
      (node (ref "V3") (pin "6") (pinfunction "6_6") (pintype "passive"))
      (node (ref "V3") (pin "7") (pinfunction "7_7") (pintype "passive"))
      (node (ref "V3") (pin "8") (pinfunction "8_8") (pintype "passive"))
      (node (ref "VREG3_OUT") (pin "+") (pinfunction "+_+") (pintype "passive"))
    )
    (net (code "66") (name "unconnected-(BMP388-3VO-Pad2)") (class "Default")
      (node (ref "BMP388") (pin "2") (pinfunction "3VO_2") (pintype "passive"))
    )
    (net (code "67") (name "unconnected-(BMP388-INT-Pad8)") (class "Default")
      (node (ref "BMP388") (pin "8") (pinfunction "INT_8") (pintype "passive"))
    )
    (net (code "68") (name "unconnected-(GPS_SMD-EXT_INT-Pad4)") (class "Default")
      (node (ref "GPS_SMD") (pin "4") (pinfunction "EXT_INT_4") (pintype "no_connect"))
    )
    (net (code "69") (name "unconnected-(GPS_SMD-LNA_EN-Pad14)") (class "Default")
      (node (ref "GPS_SMD") (pin "14") (pinfunction "LNA_EN_14") (pintype "no_connect"))
    )
    (net (code "70") (name "unconnected-(GPS_SMD-RESERVED-Pad15)") (class "Default")
      (node (ref "GPS_SMD") (pin "15") (pinfunction "RESERVED_15") (pintype "no_connect"))
    )
    (net (code "71") (name "unconnected-(GPS_SMD-RESERVED-Pad16)") (class "Default")
      (node (ref "GPS_SMD") (pin "16") (pinfunction "RESERVED_16") (pintype "no_connect"))
    )
    (net (code "72") (name "unconnected-(GPS_SMD-RESERVED-Pad17)") (class "Default")
      (node (ref "GPS_SMD") (pin "17") (pinfunction "RESERVED_17") (pintype "no_connect"))
    )
    (net (code "73") (name "unconnected-(GPS_SMD-TIMEPULSE-Pad3)") (class "Default")
      (node (ref "GPS_SMD") (pin "3") (pinfunction "TIMEPULSE_3") (pintype "no_connect"))
    )
    (net (code "74") (name "unconnected-(GPS_SMD-USB_D+-Pad6)") (class "Default")
      (node (ref "GPS_SMD") (pin "6") (pinfunction "USB_D+_6") (pintype "no_connect"))
    )
    (net (code "75") (name "unconnected-(GPS_SMD-USB_D--Pad5)") (class "Default")
      (node (ref "GPS_SMD") (pin "5") (pinfunction "USB_D-_5") (pintype "no_connect"))
    )
    (net (code "76") (name "unconnected-(GPS_SMD-VDD_USB-Pad7)") (class "Default")
      (node (ref "GPS_SMD") (pin "7") (pinfunction "VDD_USB_7") (pintype "no_connect"))
    )
    (net (code "77") (name "unconnected-(GPS_SMD-V_BKCP-Pad22)") (class "Default")
      (node (ref "GPS_SMD") (pin "22") (pinfunction "V_BKCP_22") (pintype "no_connect"))
    )
    (net (code "78") (name "unconnected-(GPS_SMD-~{RST}-Pad8)") (class "Default")
      (node (ref "GPS_SMD") (pin "8") (pinfunction "~{RST}_8") (pintype "no_connect"))
    )
    (net (code "79") (name "unconnected-(GPS_SMD-~{SAFEBOOT}-Pad1)") (class "Default")
      (node (ref "GPS_SMD") (pin "1") (pinfunction "~{SAFEBOOT}_1") (pintype "no_connect"))
    )
    (net (code "80") (name "unconnected-(TEENSY_4.1-Pad3V3_2)") (class "Default")
      (node (ref "TEENSY_4.1") (pin "3V3_2") (pinfunction "3V3_2_3V3_2") (pintype "bidirectional"))
    )
    (net (code "81") (name "unconnected-(TEENSY_4.1-PadPROG)") (class "Default")
      (node (ref "TEENSY_4.1") (pin "PROG") (pinfunction "PROG_PROG") (pintype "bidirectional"))
    )
    (net (code "82") (name "unconnected-(TEENSY_4.1-PadRESET)") (class "Default")
      (node (ref "TEENSY_4.1") (pin "RESET") (pinfunction "RESET_RESET") (pintype "bidirectional"))
    )
    (net (code "83") (name "unconnected-(TEENSY_4.1-PadU5V)") (class "Default")
      (node (ref "TEENSY_4.1") (pin "U5V") (pinfunction "U5V_U5V") (pintype "bidirectional"))
    )
    (net (code "84") (name "unconnected-(TEENSY_4.1-PadUD+)") (class "Default")
      (node (ref "TEENSY_4.1") (pin "UD+") (pinfunction "UD+_UD+") (pintype "bidirectional"))
    )
    (net (code "85") (name "unconnected-(TEENSY_4.1-PadUD-)") (class "Default")
      (node (ref "TEENSY_4.1") (pin "UD-") (pinfunction "UD-_UD-") (pintype "bidirectional"))
    )
    (net (code "86") (name "unconnected-(TEENSY_4.1-PadUGND1)") (class "Default")
      (node (ref "TEENSY_4.1") (pin "UGND1") (pinfunction "UGND1_UGND1") (pintype "bidirectional"))
    )
    (net (code "87") (name "unconnected-(TEENSY_4.1-PadUGND2)") (class "Default")
      (node (ref "TEENSY_4.1") (pin "UGND2") (pinfunction "UGND2_UGND2") (pintype "bidirectional"))
    )
    (net (code "88") (name "unconnected-(TEENSY_4.1-PadVBAT)") (class "Default")
      (node (ref "TEENSY_4.1") (pin "VBAT") (pinfunction "VBAT_VBAT") (pintype "bidirectional"))
    )
    (net (code "89") (name "unconnected-(TEENSY_4.1-PadVUSB)") (class "Default")
      (node (ref "TEENSY_4.1") (pin "VUSB") (pinfunction "VUSB_VUSB") (pintype "bidirectional"))
    )
  )
)
